# schedaSensori.net
KiCad netlist of a schematic drawn in EAGLE
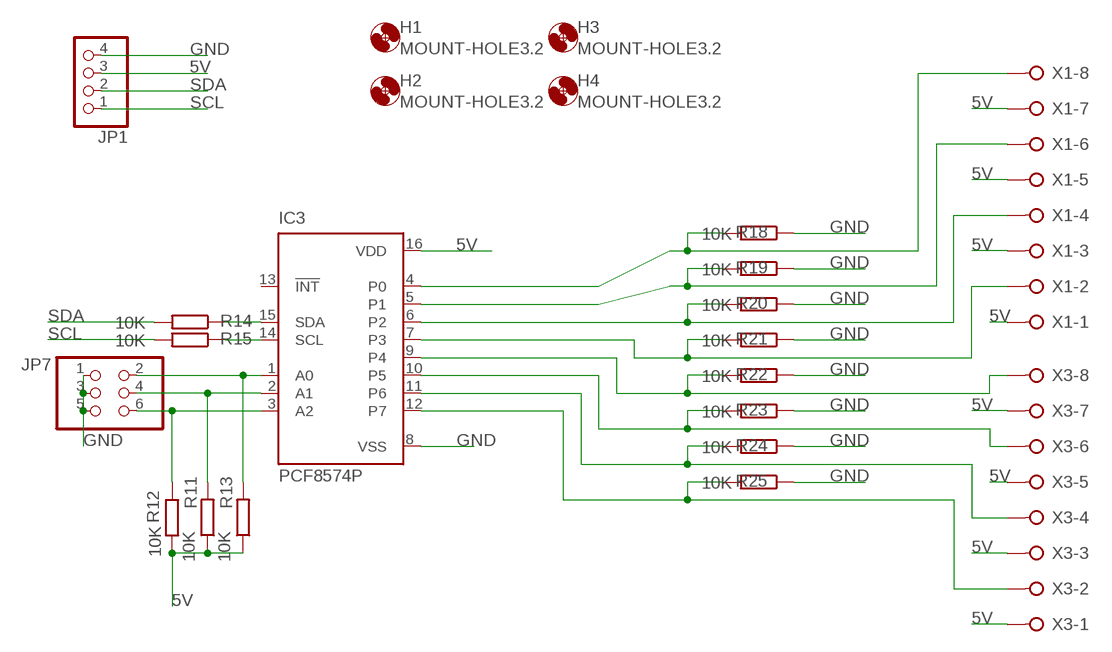
[diagram p0: schematic, sheet 1]

(export (version "E")
  (design (tool "Eeschema 10.0.6"))
  (components
    (comp (ref "H1")
      (value "MOUNT-HOLE3.2")
      (footprint "eagle-import:3,2")
      (libsource (lib "eagle-import") (part "MOUNT-HOLE3.2"))
    )
    (comp (ref "H2")
      (value "MOUNT-HOLE3.2")
      (footprint "eagle-import:3,2")
      (libsource (lib "eagle-import") (part "MOUNT-HOLE3.2"))
    )
    (comp (ref "H3")
      (value "MOUNT-HOLE3.2")
      (footprint "eagle-import:3,2")
      (libsource (lib "eagle-import") (part "MOUNT-HOLE3.2"))
    )
    (comp (ref "H4")
      (value "MOUNT-HOLE3.2")
      (footprint "eagle-import:3,2")
      (libsource (lib "eagle-import") (part "MOUNT-HOLE3.2"))
    )
    (comp (ref "IC3")
      (value "PCF8574P")
      (footprint "eagle-import:DIL16")
      (fields (field (name "MPN") "PCF8574PN"))
      (libsource (lib "eagle-import") (part "PCF8574P"))
    )
    (comp (ref "JP1")
      (value "PINHD-1X4")
      (footprint "eagle-import:1X04")
      (libsource (lib "eagle-import") (part "PINHD-1X4"))
    )
    (comp (ref "JP7")
      (value "PINHD-2X3")
      (footprint "eagle-import:2X03")
      (libsource (lib "eagle-import") (part "PINHD-2X3"))
    )
    (comp (ref "R11")
      (value "10K")
      (footprint "eagle-import:0207_10")
      (libsource (lib "eagle-import") (part "R-EU_0207/10"))
    )
    (comp (ref "R12")
      (value "10K")
      (footprint "eagle-import:0207_10")
      (libsource (lib "eagle-import") (part "R-EU_0207/10"))
    )
    (comp (ref "R13")
      (value "10K")
      (footprint "eagle-import:0207_10")
      (libsource (lib "eagle-import") (part "R-EU_0207/10"))
    )
    (comp (ref "R14")
      (value "10K")
      (footprint "eagle-import:0207_10")
      (libsource (lib "eagle-import") (part "R-EU_0207/10"))
    )
    (comp (ref "R15")
      (value "10K")
      (footprint "eagle-import:0207_10")
      (libsource (lib "eagle-import") (part "R-EU_0207/10"))
    )
    (comp (ref "R18")
      (value "10K")
      (footprint "eagle-import:0207_10")
      (libsource (lib "eagle-import") (part "R-EU_0207/10"))
    )
    (comp (ref "R19")
      (value "10K")
      (footprint "eagle-import:0207_10")
      (libsource (lib "eagle-import") (part "R-EU_0207/10"))
    )
    (comp (ref "R20")
      (value "10K")
      (footprint "eagle-import:0207_10")
      (libsource (lib "eagle-import") (part "R-EU_0207/10"))
    )
    (comp (ref "R21")
      (value "10K")
      (footprint "eagle-import:0207_10")
      (libsource (lib "eagle-import") (part "R-EU_0207/10"))
    )
    (comp (ref "R22")
      (value "10K")
      (footprint "eagle-import:0207_10")
      (libsource (lib "eagle-import") (part "R-EU_0207/10"))
    )
    (comp (ref "R23")
      (value "10K")
      (footprint "eagle-import:0207_10")
      (libsource (lib "eagle-import") (part "R-EU_0207/10"))
    )
    (comp (ref "R24")
      (value "10K")
      (footprint "eagle-import:0207_10")
      (libsource (lib "eagle-import") (part "R-EU_0207/10"))
    )
    (comp (ref "R25")
      (value "10K")
      (footprint "eagle-import:0207_10")
      (libsource (lib "eagle-import") (part "R-EU_0207/10"))
    )
    (comp (ref "X1")
      (value "W237-08P")
      (footprint "eagle-import:W237-8P")
      (libsource (lib "eagle-import") (part "W237-08P"))
    )
    (comp (ref "X3")
      (value "W237-08P")
      (footprint "eagle-import:W237-8P")
      (libsource (lib "eagle-import") (part "W237-08P"))
    )
  )
  (nets
    (net (code "1") (name "/5V") (class "Default")
      (node (ref "IC3") (pin "16") (pinfunction "VDD_16") (pintype "power_in"))
      (node (ref "JP1") (pin "3") (pinfunction "3_3") (pintype "passive"))
      (node (ref "R11") (pin "1") (pinfunction "1_1") (pintype "passive"))
      (node (ref "R12") (pin "2") (pinfunction "2_2") (pintype "passive"))
      (node (ref "R13") (pin "1") (pinfunction "1_1") (pintype "passive"))
      (node (ref "X1") (pin "1") (pinfunction "KL_1") (pintype "passive"))
      (node (ref "X1") (pin "3") (pinfunction "KL_3") (pintype "passive"))
      (node (ref "X1") (pin "5") (pinfunction "KL_5") (pintype "passive"))
      (node (ref "X1") (pin "7") (pinfunction "KL_7") (pintype "passive"))
      (node (ref "X3") (pin "1") (pinfunction "KL_1") (pintype "passive"))
      (node (ref "X3") (pin "3") (pinfunction "KL_3") (pintype "passive"))
      (node (ref "X3") (pin "5") (pinfunction "KL_5") (pintype "passive"))
      (node (ref "X3") (pin "7") (pinfunction "KL_7") (pintype "passive"))
    )
    (net (code "2") (name "/GND") (class "Default")
      (node (ref "IC3") (pin "8") (pinfunction "VSS_8") (pintype "power_in"))
      (node (ref "JP1") (pin "4") (pinfunction "4_4") (pintype "passive"))
      (node (ref "JP7") (pin "1") (pinfunction "1_1") (pintype "passive"))
      (node (ref "JP7") (pin "3") (pinfunction "3_3") (pintype "passive"))
      (node (ref "JP7") (pin "5") (pinfunction "5_5") (pintype "passive"))
      (node (ref "R18") (pin "1") (pinfunction "1_1") (pintype "passive"))
      (node (ref "R19") (pin "1") (pinfunction "1_1") (pintype "passive"))
      (node (ref "R20") (pin "1") (pinfunction "1_1") (pintype "passive"))
      (node (ref "R21") (pin "1") (pinfunction "1_1") (pintype "passive"))
      (node (ref "R22") (pin "1") (pinfunction "1_1") (pintype "passive"))
      (node (ref "R23") (pin "1") (pinfunction "1_1") (pintype "passive"))
      (node (ref "R24") (pin "1") (pinfunction "1_1") (pintype "passive"))
      (node (ref "R25") (pin "1") (pinfunction "1_1") (pintype "passive"))
    )
    (net (code "3") (name "/SCL") (class "Default")
      (node (ref "JP1") (pin "1") (pinfunction "1_1") (pintype "passive"))
      (node (ref "R15") (pin "2") (pinfunction "2_2") (pintype "passive"))
    )
    (net (code "4") (name "/SDA") (class "Default")
      (node (ref "JP1") (pin "2") (pinfunction "2_2") (pintype "passive"))
      (node (ref "R14") (pin "2") (pinfunction "2_2") (pintype "passive"))
    )
    (net (code "5") (name "Net-(IC3-A0)") (class "Default")
      (node (ref "IC3") (pin "1") (pinfunction "A0_1") (pintype "input"))
      (node (ref "JP7") (pin "2") (pinfunction "2_2") (pintype "passive"))
      (node (ref "R13") (pin "2") (pinfunction "2_2") (pintype "passive"))
    )
    (net (code "6") (name "Net-(IC3-A1)") (class "Default")
      (node (ref "IC3") (pin "2") (pinfunction "A1_2") (pintype "input"))
      (node (ref "JP7") (pin "4") (pinfunction "4_4") (pintype "passive"))
      (node (ref "R11") (pin "2") (pinfunction "2_2") (pintype "passive"))
    )
    (net (code "7") (name "Net-(IC3-A2)") (class "Default")
      (node (ref "IC3") (pin "3") (pinfunction "A2_3") (pintype "input"))
      (node (ref "JP7") (pin "6") (pinfunction "6_6") (pintype "passive"))
      (node (ref "R12") (pin "1") (pinfunction "1_1") (pintype "passive"))
    )
    (net (code "8") (name "Net-(IC3-P0)") (class "Default")
      (node (ref "IC3") (pin "4") (pinfunction "P0_4") (pintype "bidirectional"))
      (node (ref "R18") (pin "2") (pinfunction "2_2") (pintype "passive"))
      (node (ref "X1") (pin "8") (pinfunction "KL_8") (pintype "passive"))
    )
    (net (code "9") (name "Net-(IC3-P1)") (class "Default")
      (node (ref "IC3") (pin "5") (pinfunction "P1_5") (pintype "bidirectional"))
      (node (ref "R19") (pin "2") (pinfunction "2_2") (pintype "passive"))
      (node (ref "X1") (pin "6") (pinfunction "KL_6") (pintype "passive"))
    )
    (net (code "10") (name "Net-(IC3-P2)") (class "Default")
      (node (ref "IC3") (pin "6") (pinfunction "P2_6") (pintype "bidirectional"))
      (node (ref "R20") (pin "2") (pinfunction "2_2") (pintype "passive"))
      (node (ref "X1") (pin "4") (pinfunction "KL_4") (pintype "passive"))
    )
    (net (code "11") (name "Net-(IC3-P3)") (class "Default")
      (node (ref "IC3") (pin "7") (pinfunction "P3_7") (pintype "bidirectional"))
      (node (ref "R21") (pin "2") (pinfunction "2_2") (pintype "passive"))
      (node (ref "X1") (pin "2") (pinfunction "KL_2") (pintype "passive"))
    )
    (net (code "12") (name "Net-(IC3-P4)") (class "Default")
      (node (ref "IC3") (pin "9") (pinfunction "P4_9") (pintype "bidirectional"))
      (node (ref "R22") (pin "2") (pinfunction "2_2") (pintype "passive"))
      (node (ref "X3") (pin "8") (pinfunction "KL_8") (pintype "passive"))
    )
    (net (code "13") (name "Net-(IC3-P5)") (class "Default")
      (node (ref "IC3") (pin "10") (pinfunction "P5_10") (pintype "bidirectional"))
      (node (ref "R23") (pin "2") (pinfunction "2_2") (pintype "passive"))
      (node (ref "X3") (pin "6") (pinfunction "KL_6") (pintype "passive"))
    )
    (net (code "14") (name "Net-(IC3-P6)") (class "Default")
      (node (ref "IC3") (pin "11") (pinfunction "P6_11") (pintype "bidirectional"))
      (node (ref "R24") (pin "2") (pinfunction "2_2") (pintype "passive"))
      (node (ref "X3") (pin "4") (pinfunction "KL_4") (pintype "passive"))
    )
    (net (code "15") (name "Net-(IC3-P7)") (class "Default")
      (node (ref "IC3") (pin "12") (pinfunction "P7_12") (pintype "bidirectional"))
      (node (ref "R25") (pin "2") (pinfunction "2_2") (pintype "passive"))
      (node (ref "X3") (pin "2") (pinfunction "KL_2") (pintype "passive"))
    )
    (net (code "16") (name "Net-(IC3-SCL)") (class "Default")
      (node (ref "IC3") (pin "14") (pinfunction "SCL_14") (pintype "input"))
      (node (ref "R15") (pin "1") (pinfunction "1_1") (pintype "passive"))
    )
    (net (code "17") (name "Net-(IC3-SDA)") (class "Default")
      (node (ref "IC3") (pin "15") (pinfunction "SDA_15") (pintype "bidirectional"))
      (node (ref "R14") (pin "1") (pinfunction "1_1") (pintype "passive"))
    )
    (net (code "18") (name "unconnected-(IC3-~{INT}-Pad13)") (class "Default")
      (node (ref "IC3") (pin "13") (pinfunction "~{INT}_13") (pintype "output"))
    )
  )
)
